# schematic.net
KiCad netlist of a schematic drawn in EAGLE
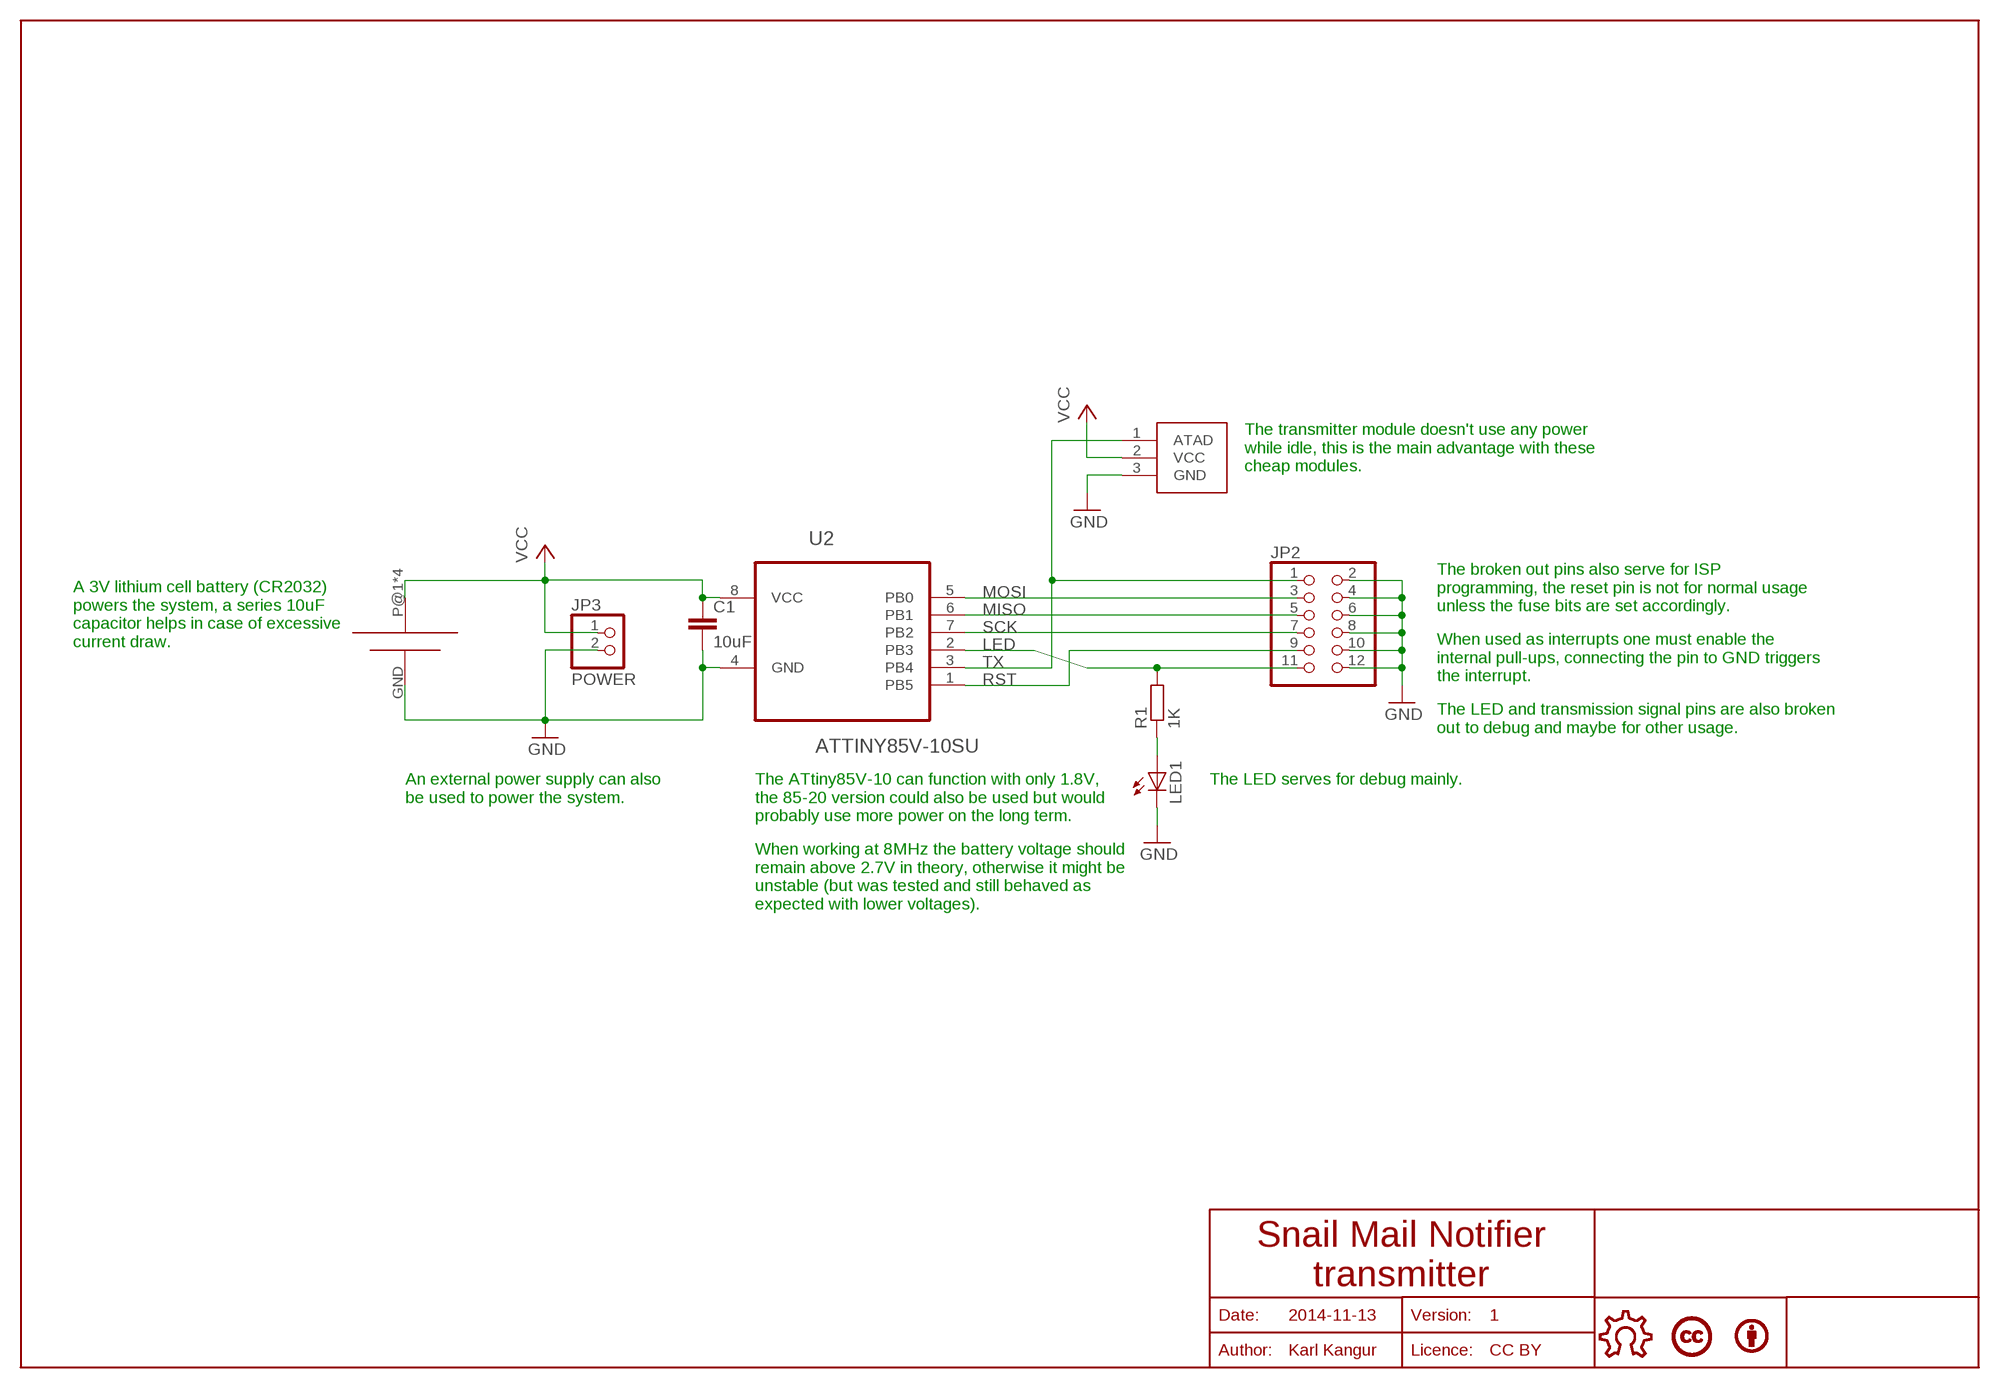
[diagram p0: schematic, sheet 1]

(export (version "E")
  (design (tool "Eeschema 10.0.6"))
  (components
    (comp (ref "BY1")
      (value "BYBOTTOM")
      (footprint "eagle-import:BY")
      (libsource (lib "eagle-import") (part "BYBOTTOM"))
    )
    (comp (ref "C1")
      (value "10uF")
      (footprint "eagle-import:C0805")
      (libsource (lib "eagle-import") (part "C-EUC0805"))
    )
    (comp (ref "JP2")
      (value "PINHD-2X6")
      (footprint "eagle-import:2X06")
      (libsource (lib "eagle-import") (part "PINHD-2X6"))
    )
    (comp (ref "JP3")
      (value "POWER")
      (footprint "eagle-import:1X02")
      (libsource (lib "eagle-import") (part "PINHD-1X2"))
    )
    (comp (ref "LED1")
      (value "LEDCHIPLED_0805")
      (footprint "eagle-import:CHIPLED_0805")
      (libsource (lib "eagle-import") (part "LEDCHIPLED_0805"))
    )
    (comp (ref "LICENCE1")
      (value "LICENCECC-BOTTOM")
      (footprint "eagle-import:CREATIVE-COMMONS")
      (libsource (lib "eagle-import") (part "LICENCECC-BOTTOM"))
    )
    (comp (ref "R1")
      (value "1K")
      (footprint "eagle-import:R0805")
      (libsource (lib "eagle-import") (part "R-EU_R0805"))
    )
    (comp (ref "U$1")
      (value "RF_LINK_TRANSMITTER")
      (footprint "eagle-import:RF_LINK_TRANSMITTER")
      (libsource (lib "eagle-import") (part "RF_LINK_TRANSMITTER"))
    )
    (comp (ref "U$2")
      (value "CR2032-BATTERY-HOLDER")
      (footprint "eagle-import:CR2032-BATTERY-HOLDER-PCB")
      (libsource (lib "eagle-import") (part "CR2032-BATTERY-HOLDER"))
    )
    (comp (ref "U$5")
      (value "OPEN-HARDWARE-LOGOBOTTOM-SMALL")
      (footprint "eagle-import:OPEN-HARDWARE-BOTTOM-SMALL")
      (libsource (lib "eagle-import") (part "OPEN-HARDWARE-LOGOBOTTOM-SMALL"))
    )
    (comp (ref "U2")
      (value "ATTINY85V-10SU")
      (footprint "eagle-import:SOIC127P798X216-8N")
      (libsource (lib "eagle-import") (part "ATTINY85V-10SU"))
    )
  )
  (nets
    (net (code "1") (name "/LED") (class "Default")
      (node (ref "JP2") (pin "11") (pinfunction "11_11") (pintype "passive"))
      (node (ref "R1") (pin "2") (pinfunction "2_2") (pintype "passive"))
      (node (ref "U2") (pin "2") (pinfunction "PB3_2") (pintype "bidirectional"))
    )
    (net (code "2") (name "/MISO") (class "Default")
      (node (ref "JP2") (pin "5") (pinfunction "5_5") (pintype "passive"))
      (node (ref "U2") (pin "6") (pinfunction "PB1_6") (pintype "bidirectional"))
    )
    (net (code "3") (name "/MOSI") (class "Default")
      (node (ref "JP2") (pin "3") (pinfunction "3_3") (pintype "passive"))
      (node (ref "U2") (pin "5") (pinfunction "PB0_5") (pintype "bidirectional"))
    )
    (net (code "4") (name "/RST") (class "Default")
      (node (ref "JP2") (pin "9") (pinfunction "9_9") (pintype "passive"))
      (node (ref "U2") (pin "1") (pinfunction "PB5_1") (pintype "bidirectional"))
    )
    (net (code "5") (name "/SCK") (class "Default")
      (node (ref "JP2") (pin "7") (pinfunction "7_7") (pintype "passive"))
      (node (ref "U2") (pin "7") (pinfunction "PB2_7") (pintype "bidirectional"))
    )
    (net (code "6") (name "/TX") (class "Default")
      (node (ref "JP2") (pin "1") (pinfunction "1_1") (pintype "passive"))
      (node (ref "U$1") (pin "1") (pinfunction "ATAD_1") (pintype "bidirectional"))
      (node (ref "U2") (pin "3") (pinfunction "PB4_3") (pintype "bidirectional"))
    )
    (net (code "7") (name "GND") (class "Default")
      (node (ref "C1") (pin "2") (pinfunction "2_2") (pintype "passive"))
      (node (ref "JP2") (pin "10") (pinfunction "10_10") (pintype "passive"))
      (node (ref "JP2") (pin "12") (pinfunction "12_12") (pintype "passive"))
      (node (ref "JP2") (pin "2") (pinfunction "2_2") (pintype "passive"))
      (node (ref "JP2") (pin "4") (pinfunction "4_4") (pintype "passive"))
      (node (ref "JP2") (pin "6") (pinfunction "6_6") (pintype "passive"))
      (node (ref "JP2") (pin "8") (pinfunction "8_8") (pintype "passive"))
      (node (ref "JP3") (pin "2") (pinfunction "2_2") (pintype "passive"))
      (node (ref "LED1") (pin "C") (pinfunction "C_C") (pintype "passive"))
      (node (ref "U$1") (pin "3") (pinfunction "GND_3") (pintype "bidirectional"))
      (node (ref "U$2") (pin "GND") (pinfunction "N_GND") (pintype "bidirectional"))
      (node (ref "U2") (pin "4") (pinfunction "GND_4") (pintype "passive"))
    )
    (net (code "8") (name "Net-(LED1-PadA)") (class "Default")
      (node (ref "LED1") (pin "A") (pinfunction "A_A") (pintype "passive"))
      (node (ref "R1") (pin "1") (pinfunction "1_1") (pintype "passive"))
    )
    (net (code "9") (name "VCC") (class "Default")
      (node (ref "C1") (pin "1") (pinfunction "1_1") (pintype "passive"))
      (node (ref "JP3") (pin "1") (pinfunction "1_1") (pintype "passive"))
      (node (ref "U$1") (pin "2") (pinfunction "VCC_2") (pintype "bidirectional"))
      (node (ref "U$2") (pin "P@1") (pinfunction "P_P@1") (pintype "bidirectional"))
      (node (ref "U$2") (pin "P@2") (pinfunction "P_P@2") (pintype "bidirectional"))
      (node (ref "U$2") (pin "P@3") (pinfunction "P_P@3") (pintype "bidirectional"))
      (node (ref "U$2") (pin "P@4") (pinfunction "P_P@4") (pintype "bidirectional"))
      (node (ref "U2") (pin "8") (pinfunction "VCC_8") (pintype "power_in"))
    )
  )
)
